# CAN.net
KiCad netlist of a schematic drawn in Altium Designer
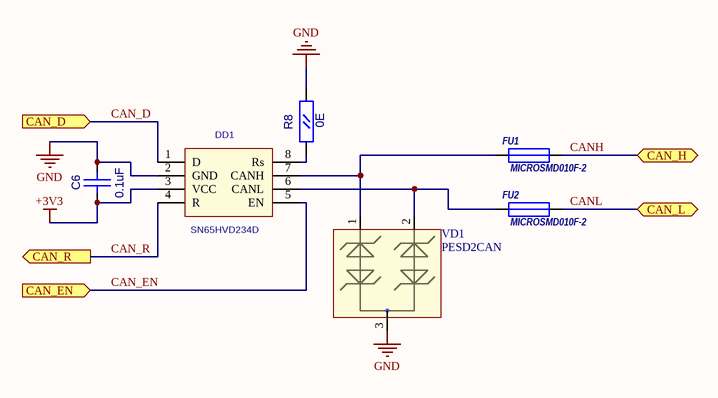
[diagram p0: CAN.SchDoc]

(export (version "E")
  (design (tool "Eeschema 10.0.6"))
  (components
    (comp (ref "C6")
      (value "0.1uF")
      (footprint "CC0603")
      (description "CC0603")
      (libsource (lib "gprs_modem_2") (part "CC0603"))
    )
    (comp (ref "DD1")
      (value "SN65HVD234D")
      (footprint "SO-8")
      (description "CAN Transceiver")
      (libsource (lib "gprs_modem_2") (part "SN65HVD234D"))
    )
    (comp (ref "FU1")
      (value "MICROSMD010F-2")
      (footprint "RC1210")
      (description "MICROSMD")
      (libsource (lib "gprs_modem_2") (part "MICROSMD"))
    )
    (comp (ref "FU2")
      (value "MICROSMD010F-2")
      (footprint "RC1210")
      (description "MICROSMD")
      (libsource (lib "gprs_modem_2") (part "MICROSMD"))
    )
    (comp (ref "R8")
      (value "0E")
      (footprint "RC0603")
      (description "RC0603")
      (libsource (lib "gprs_modem_2") (part "RC0603"))
    )
    (comp (ref "VD1")
      (value "PESD2CAN")
      (footprint "SOT-23(123)")
      (description "TVS for CAN")
      (libsource (lib "gprs_modem_2") (part "PESD2CAN"))
    )
  )
  (nets
    (net (code "1") (name "+3V3") (class "Default")
      (node (ref "C6") (pin "1") (pinfunction "A_1") (pintype "passive"))
      (node (ref "DD1") (pin "3") (pinfunction "VCC_3") (pintype "passive"))
    )
    (net (code "2") (name "/CANH") (class "Default") (node (ref "FU1") (pin "2") (pintype "passive")))
    (net (code "3") (name "/CANL") (class "Default") (node (ref "FU2") (pin "2") (pintype "passive")))
    (net (code "4") (name "/CAN_D") (class "Default")
      (node (ref "DD1") (pin "1") (pinfunction "D_1") (pintype "passive"))
    )
    (net (code "5") (name "/CAN_EN") (class "Default")
      (node (ref "DD1") (pin "5") (pinfunction "EN_5") (pintype "passive"))
    )
    (net (code "6") (name "/CAN_R") (class "Default")
      (node (ref "DD1") (pin "4") (pinfunction "R_4") (pintype "passive"))
    )
    (net (code "7") (name "GND") (class "Default")
      (node (ref "C6") (pin "2") (pinfunction "B_2") (pintype "passive"))
      (node (ref "DD1") (pin "2") (pinfunction "GND_2") (pintype "passive"))
      (node (ref "R8") (pin "2") (pinfunction "B_2") (pintype "passive"))
      (node (ref "VD1") (pin "3") (pinfunction "3_3") (pintype "passive"))
    )
    (net (code "8") (name "Net-(DD1-CANH)") (class "Default")
      (node (ref "DD1") (pin "7") (pinfunction "CANH_7") (pintype "passive"))
      (node (ref "FU1") (pin "1") (pintype "passive"))
      (node (ref "VD1") (pin "1") (pinfunction "1_1") (pintype "passive"))
    )
    (net (code "9") (name "Net-(DD1-CANL)") (class "Default")
      (node (ref "DD1") (pin "6") (pinfunction "CANL_6") (pintype "passive"))
      (node (ref "FU2") (pin "1") (pintype "passive"))
      (node (ref "VD1") (pin "2") (pinfunction "2_2") (pintype "passive"))
    )
    (net (code "10") (name "Net-(DD1-Rs)") (class "Default")
      (node (ref "DD1") (pin "8") (pinfunction "Rs_8") (pintype "passive"))
      (node (ref "R8") (pin "1") (pinfunction "A_1") (pintype "passive"))
    )
  )
)
